# project_1.net
KiCad netlist of a schematic drawn in Altium Designer
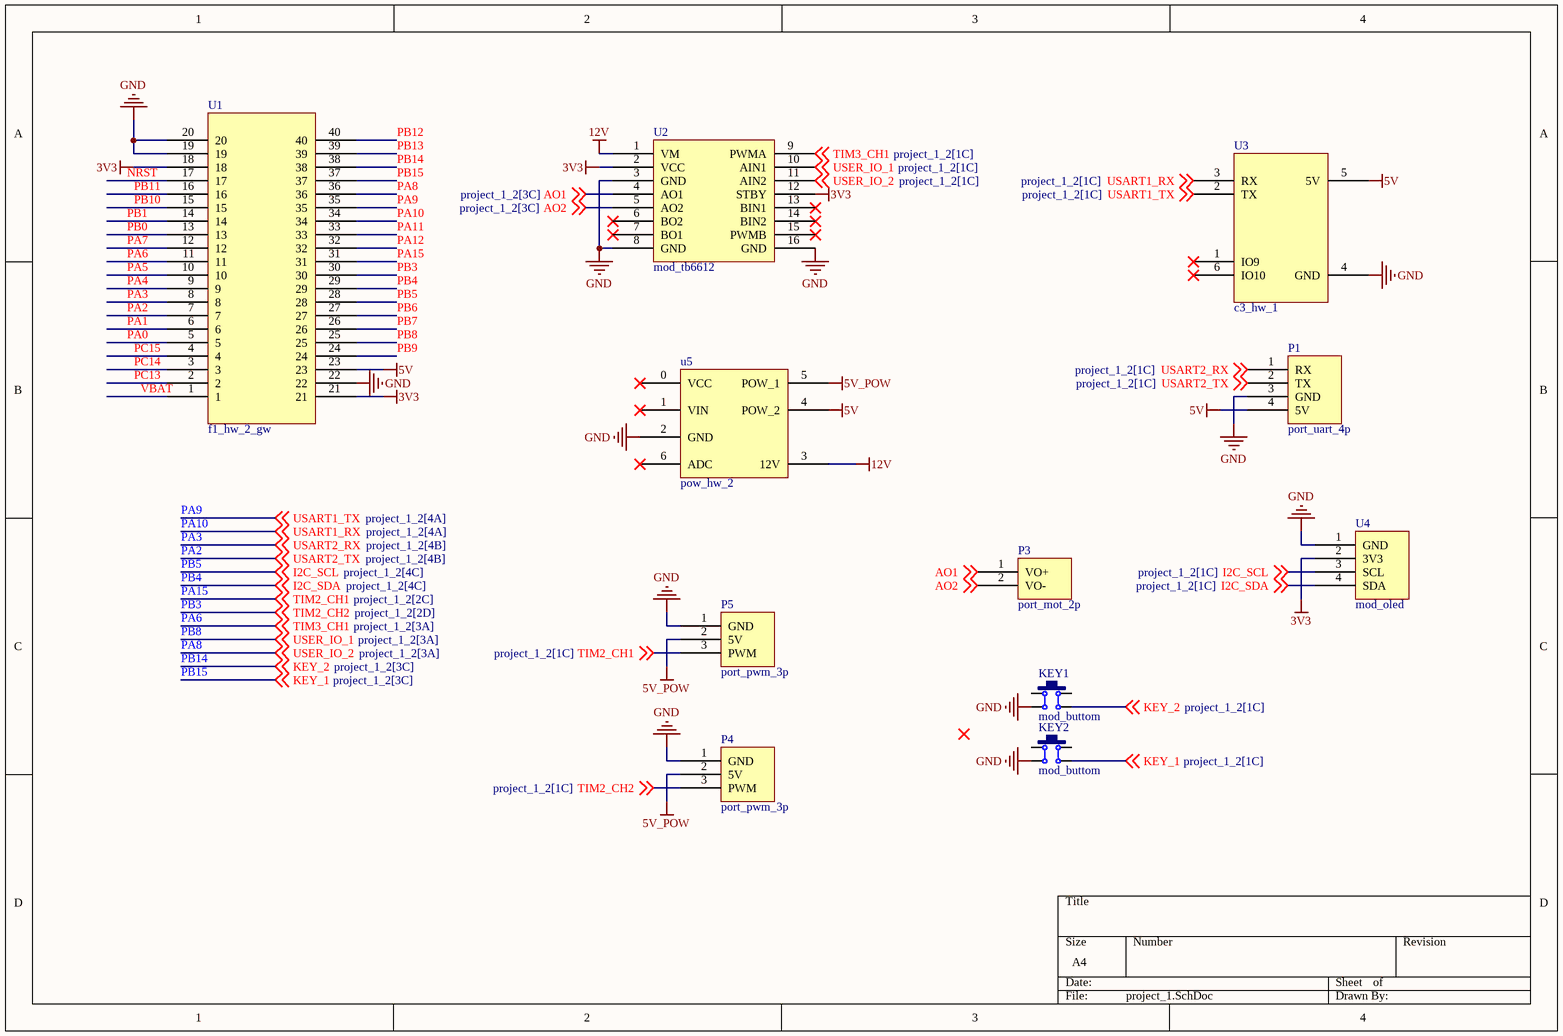
[diagram p0: project_1.SchDoc]

(export (version "E")
  (design (tool "Eeschema 10.0.6"))
  (components
    (comp (ref "KEY1")
      (value "mod_buttom")
      (footprint "MOD_BUTTOM")
      (description "6*6*4.3按键")
      (libsource (lib "userLib") (part "mod_buttom"))
    )
    (comp (ref "KEY2")
      (value "mod_buttom")
      (footprint "MOD_BUTTOM")
      (description "6*6*4.3按键")
      (libsource (lib "userLib") (part "mod_buttom"))
    )
    (comp (ref "P1")
      (value "port_uart_4p")
      (footprint "XH2.54_4P")
      (description "串口接口/SPP蓝牙模块\r\nXH2.54弯排针4p/4p排母")
      (libsource (lib "userLib") (part "port_uart_4p"))
    )
    (comp (ref "P3")
      (value "port_mot_2p")
      (footprint "XH2.54_2P")
      (description "开环直流电机接口\r\nXH2.54弯排针2p")
      (libsource (lib "userLib") (part "port_mot_2p"))
    )
    (comp (ref "P4")
      (value "port_pwm_3p")
      (footprint "XH2.54_3P")
      (description "舵机接口\r\nXH2.54弯排针3p")
      (libsource (lib "userLib") (part "port_pwm_3p"))
    )
    (comp (ref "P5")
      (value "port_pwm_3p")
      (footprint "XH2.54_3P")
      (description "舵机接口\r\nXH2.54弯排针3p")
      (libsource (lib "userLib") (part "port_pwm_3p"))
    )
    (comp (ref "U1")
      (value "f1_hw_2_gw")
      (footprint "F1_HW_2_GW")
      (libsource (lib "userLib") (part "f1_hw_2_gw"))
    )
    (comp (ref "U2")
      (value "mod_tb6612")
      (footprint "MOD_TB6612")
      (description "TB6612模块\r\n8p排母*2")
      (libsource (lib "userLib") (part "mod_tb6612"))
    )
    (comp (ref "U3")
      (value "c3_hw_1")
      (footprint "C3_HW_1")
      (description "ESP32C3蓝牙模块\r\n6p排母")
      (libsource (lib "userLib") (part "c3_hw_1"))
    )
    (comp (ref "U4")
      (value "mod_oled")
      (footprint "mod_oled")
      (description "外购屏幕模块")
      (libsource (lib "userLib") (part "mod_oled"))
    )
    (comp (ref "u5")
      (value "pow_hw_2")
      (footprint "POW_HW_2")
      (description "两路升降压电源模块\r\n6p排母*2")
      (libsource (lib "userLib") (part "pow_hw_2"))
    )
  )
  (nets
    (net (code "1") (name "/NRST") (class "Default")
      (node (ref "U1") (pin "17") (pinfunction "17_17") (pintype "passive"))
    )
    (net (code "2") (name "/PA0") (class "Default")
      (node (ref "U1") (pin "5") (pinfunction "5_5") (pintype "passive"))
    )
    (net (code "3") (name "/PA1") (class "Default")
      (node (ref "U1") (pin "6") (pinfunction "6_6") (pintype "passive"))
    )
    (net (code "4") (name "/PA4") (class "Default")
      (node (ref "U1") (pin "9") (pinfunction "9_9") (pintype "passive"))
    )
    (net (code "5") (name "/PA5") (class "Default")
      (node (ref "U1") (pin "10") (pinfunction "10_10") (pintype "passive"))
    )
    (net (code "6") (name "/PA7") (class "Default")
      (node (ref "U1") (pin "12") (pinfunction "12_12") (pintype "passive"))
    )
    (net (code "7") (name "/PA11") (class "Default")
      (node (ref "U1") (pin "33") (pinfunction "33_33") (pintype "passive"))
    )
    (net (code "8") (name "/PA12") (class "Default")
      (node (ref "U1") (pin "32") (pinfunction "32_32") (pintype "passive"))
    )
    (net (code "9") (name "/PB0") (class "Default")
      (node (ref "U1") (pin "13") (pinfunction "13_13") (pintype "passive"))
    )
    (net (code "10") (name "/PB1") (class "Default")
      (node (ref "U1") (pin "14") (pinfunction "14_14") (pintype "passive"))
    )
    (net (code "11") (name "/PB6") (class "Default")
      (node (ref "U1") (pin "27") (pinfunction "27_27") (pintype "passive"))
    )
    (net (code "12") (name "/PB7") (class "Default")
      (node (ref "U1") (pin "26") (pinfunction "26_26") (pintype "passive"))
    )
    (net (code "13") (name "/PB9") (class "Default")
      (node (ref "U1") (pin "24") (pinfunction "24_24") (pintype "passive"))
    )
    (net (code "14") (name "/PB10") (class "Default")
      (node (ref "U1") (pin "15") (pinfunction "15_15") (pintype "passive"))
    )
    (net (code "15") (name "/PB11") (class "Default")
      (node (ref "U1") (pin "16") (pinfunction "16_16") (pintype "passive"))
    )
    (net (code "16") (name "/PB12") (class "Default")
      (node (ref "U1") (pin "40") (pinfunction "40_40") (pintype "passive"))
    )
    (net (code "17") (name "/PB13") (class "Default")
      (node (ref "U1") (pin "39") (pinfunction "39_39") (pintype "passive"))
    )
    (net (code "18") (name "/PC13") (class "Default")
      (node (ref "U1") (pin "2") (pinfunction "2_2") (pintype "passive"))
    )
    (net (code "19") (name "/PC14") (class "Default")
      (node (ref "U1") (pin "3") (pinfunction "3_3") (pintype "passive"))
    )
    (net (code "20") (name "/PC15") (class "Default")
      (node (ref "U1") (pin "4") (pinfunction "4_4") (pintype "passive"))
    )
    (net (code "21") (name "/VBAT") (class "Default")
      (node (ref "U1") (pin "1") (pinfunction "1_1") (pintype "passive"))
    )
    (net (code "22") (name "3V3") (class "Default")
      (node (ref "U1") (pin "18") (pinfunction "18_18") (pintype "passive"))
      (node (ref "U1") (pin "21") (pinfunction "21_21") (pintype "passive"))
      (node (ref "U2") (pin "12") (pinfunction "STBY_12") (pintype "passive"))
      (node (ref "U2") (pin "2") (pinfunction "VCC_2") (pintype "passive"))
      (node (ref "U4") (pin "2") (pinfunction "3V3_2") (pintype "passive"))
    )
    (net (code "23") (name "5V") (class "Default")
      (node (ref "P1") (pin "4") (pinfunction "5V_4") (pintype "passive"))
      (node (ref "U1") (pin "23") (pinfunction "23_23") (pintype "passive"))
      (node (ref "U3") (pin "5") (pinfunction "5V_5") (pintype "passive"))
      (node (ref "u5") (pin "4") (pinfunction "POW_2_4") (pintype "passive"))
    )
    (net (code "24") (name "5V_POW") (class "Default")
      (node (ref "P4") (pin "2") (pinfunction "5V_2") (pintype "passive"))
      (node (ref "P5") (pin "2") (pinfunction "5V_2") (pintype "passive"))
      (node (ref "u5") (pin "5") (pinfunction "POW_1_5") (pintype "passive"))
    )
    (net (code "25") (name "12V") (class "Default")
      (node (ref "U2") (pin "1") (pinfunction "VM_1") (pintype "passive"))
      (node (ref "u5") (pin "3") (pinfunction "12V_3") (pintype "passive"))
    )
    (net (code "26") (name "AO1") (class "Default")
      (node (ref "P3") (pin "1") (pinfunction "VO+_1") (pintype "passive"))
      (node (ref "U2") (pin "4") (pinfunction "AO1_4") (pintype "passive"))
    )
    (net (code "27") (name "AO2") (class "Default")
      (node (ref "P3") (pin "2") (pinfunction "VO-_2") (pintype "passive"))
      (node (ref "U2") (pin "5") (pinfunction "AO2_5") (pintype "passive"))
    )
    (net (code "28") (name "GND") (class "Default")
      (node (ref "KEY1") (pin "4") (pinfunction "4_4") (pintype "passive"))
      (node (ref "KEY2") (pin "4") (pinfunction "4_4") (pintype "passive"))
      (node (ref "P1") (pin "3") (pinfunction "GND_3") (pintype "passive"))
      (node (ref "P4") (pin "1") (pinfunction "GND_1") (pintype "passive"))
      (node (ref "P5") (pin "1") (pinfunction "GND_1") (pintype "passive"))
      (node (ref "U1") (pin "19") (pinfunction "19_19") (pintype "passive"))
      (node (ref "U1") (pin "20") (pinfunction "20_20") (pintype "passive"))
      (node (ref "U1") (pin "22") (pinfunction "22_22") (pintype "passive"))
      (node (ref "U2") (pin "16") (pinfunction "GND_16") (pintype "passive"))
      (node (ref "U2") (pin "3") (pinfunction "GND_3") (pintype "passive"))
      (node (ref "U2") (pin "8") (pinfunction "GND_8") (pintype "passive"))
      (node (ref "U3") (pin "4") (pinfunction "GND_4") (pintype "passive"))
      (node (ref "U4") (pin "1") (pinfunction "GND_1") (pintype "passive"))
      (node (ref "u5") (pin "2") (pinfunction "GND_2") (pintype "passive"))
    )
    (net (code "29") (name "I2C_SCL") (class "Default")
      (node (ref "U1") (pin "28") (pinfunction "28_28") (pintype "passive"))
      (node (ref "U4") (pin "3") (pinfunction "SCL_3") (pintype "passive"))
    )
    (net (code "30") (name "I2C_SDA") (class "Default")
      (node (ref "U1") (pin "29") (pinfunction "29_29") (pintype "passive"))
      (node (ref "U4") (pin "4") (pinfunction "SDA_4") (pintype "passive"))
    )
    (net (code "31") (name "KEY_1") (class "Default")
      (node (ref "KEY2") (pin "3") (pinfunction "3_3") (pintype "passive"))
      (node (ref "U1") (pin "37") (pinfunction "37_37") (pintype "passive"))
    )
    (net (code "32") (name "KEY_2") (class "Default")
      (node (ref "KEY1") (pin "3") (pinfunction "3_3") (pintype "passive"))
      (node (ref "U1") (pin "38") (pinfunction "38_38") (pintype "passive"))
    )
    (net (code "33") (name "TIM2_CH1") (class "Default")
      (node (ref "P5") (pin "3") (pinfunction "PWM_3") (pintype "passive"))
      (node (ref "U1") (pin "31") (pinfunction "31_31") (pintype "passive"))
    )
    (net (code "34") (name "TIM2_CH2") (class "Default")
      (node (ref "P4") (pin "3") (pinfunction "PWM_3") (pintype "passive"))
      (node (ref "U1") (pin "30") (pinfunction "30_30") (pintype "passive"))
    )
    (net (code "35") (name "TIM3_CH1") (class "Default")
      (node (ref "U1") (pin "11") (pinfunction "11_11") (pintype "passive"))
      (node (ref "U2") (pin "9") (pinfunction "PWMA_9") (pintype "passive"))
    )
    (net (code "36") (name "USART1_RX") (class "Default")
      (node (ref "U1") (pin "34") (pinfunction "34_34") (pintype "passive"))
      (node (ref "U3") (pin "3") (pinfunction "RX_3") (pintype "passive"))
    )
    (net (code "37") (name "USART1_TX") (class "Default")
      (node (ref "U1") (pin "35") (pinfunction "35_35") (pintype "passive"))
      (node (ref "U3") (pin "2") (pinfunction "TX_2") (pintype "passive"))
    )
    (net (code "38") (name "USART2_RX") (class "Default")
      (node (ref "P1") (pin "1") (pinfunction "RX_1") (pintype "passive"))
      (node (ref "U1") (pin "8") (pinfunction "8_8") (pintype "passive"))
    )
    (net (code "39") (name "USART2_TX") (class "Default")
      (node (ref "P1") (pin "2") (pinfunction "TX_2") (pintype "passive"))
      (node (ref "U1") (pin "7") (pinfunction "7_7") (pintype "passive"))
    )
    (net (code "40") (name "USER_IO_1") (class "Default")
      (node (ref "U1") (pin "25") (pinfunction "25_25") (pintype "passive"))
      (node (ref "U2") (pin "10") (pinfunction "AIN1_10") (pintype "passive"))
    )
    (net (code "41") (name "USER_IO_2") (class "Default")
      (node (ref "U1") (pin "36") (pinfunction "36_36") (pintype "passive"))
      (node (ref "U2") (pin "11") (pinfunction "AIN2_11") (pintype "passive"))
    )
    (net (code "42") (name "unconnected-(KEY1-Pad1)") (class "Default")
      (node (ref "KEY1") (pin "1") (pinfunction "1_1") (pintype "passive"))
    )
    (net (code "43") (name "unconnected-(KEY1-Pad2)") (class "Default")
      (node (ref "KEY1") (pin "2") (pinfunction "2_2") (pintype "passive"))
    )
    (net (code "44") (name "unconnected-(KEY2-Pad1)") (class "Default")
      (node (ref "KEY2") (pin "1") (pinfunction "1_1") (pintype "passive"))
    )
    (net (code "45") (name "unconnected-(KEY2-Pad2)") (class "Default")
      (node (ref "KEY2") (pin "2") (pinfunction "2_2") (pintype "passive"))
    )
    (net (code "46") (name "unconnected-(U2-BIN1-Pad13)") (class "Default")
      (node (ref "U2") (pin "13") (pinfunction "BIN1_13") (pintype "passive+no_connect"))
    )
    (net (code "47") (name "unconnected-(U2-BIN2-Pad14)") (class "Default")
      (node (ref "U2") (pin "14") (pinfunction "BIN2_14") (pintype "passive+no_connect"))
    )
    (net (code "48") (name "unconnected-(U2-BO1-Pad7)") (class "Default")
      (node (ref "U2") (pin "7") (pinfunction "BO1_7") (pintype "passive+no_connect"))
    )
    (net (code "49") (name "unconnected-(U2-BO2-Pad6)") (class "Default")
      (node (ref "U2") (pin "6") (pinfunction "BO2_6") (pintype "passive+no_connect"))
    )
    (net (code "50") (name "unconnected-(U2-PWMB-Pad15)") (class "Default")
      (node (ref "U2") (pin "15") (pinfunction "PWMB_15") (pintype "passive+no_connect"))
    )
    (net (code "51") (name "unconnected-(U3-IO9-Pad1)") (class "Default")
      (node (ref "U3") (pin "1") (pinfunction "IO9_1") (pintype "passive+no_connect"))
    )
    (net (code "52") (name "unconnected-(U3-IO10-Pad6)") (class "Default")
      (node (ref "U3") (pin "6") (pinfunction "IO10_6") (pintype "passive+no_connect"))
    )
    (net (code "53") (name "unconnected-(u5-ADC-Pad6)") (class "Default")
      (node (ref "u5") (pin "6") (pinfunction "ADC_6") (pintype "passive+no_connect"))
    )
    (net (code "54") (name "unconnected-(u5-VCC-Pad0)") (class "Default")
      (node (ref "u5") (pin "0") (pinfunction "VCC_0") (pintype "passive+no_connect"))
    )
    (net (code "55") (name "unconnected-(u5-VIN-Pad1)") (class "Default")
      (node (ref "u5") (pin "1") (pinfunction "VIN_1") (pintype "passive+no_connect"))
    )
  )
)
